# KNX-MCU-CONTROL_V0_2.net
KiCad netlist of a schematic drawn in Altium Designer
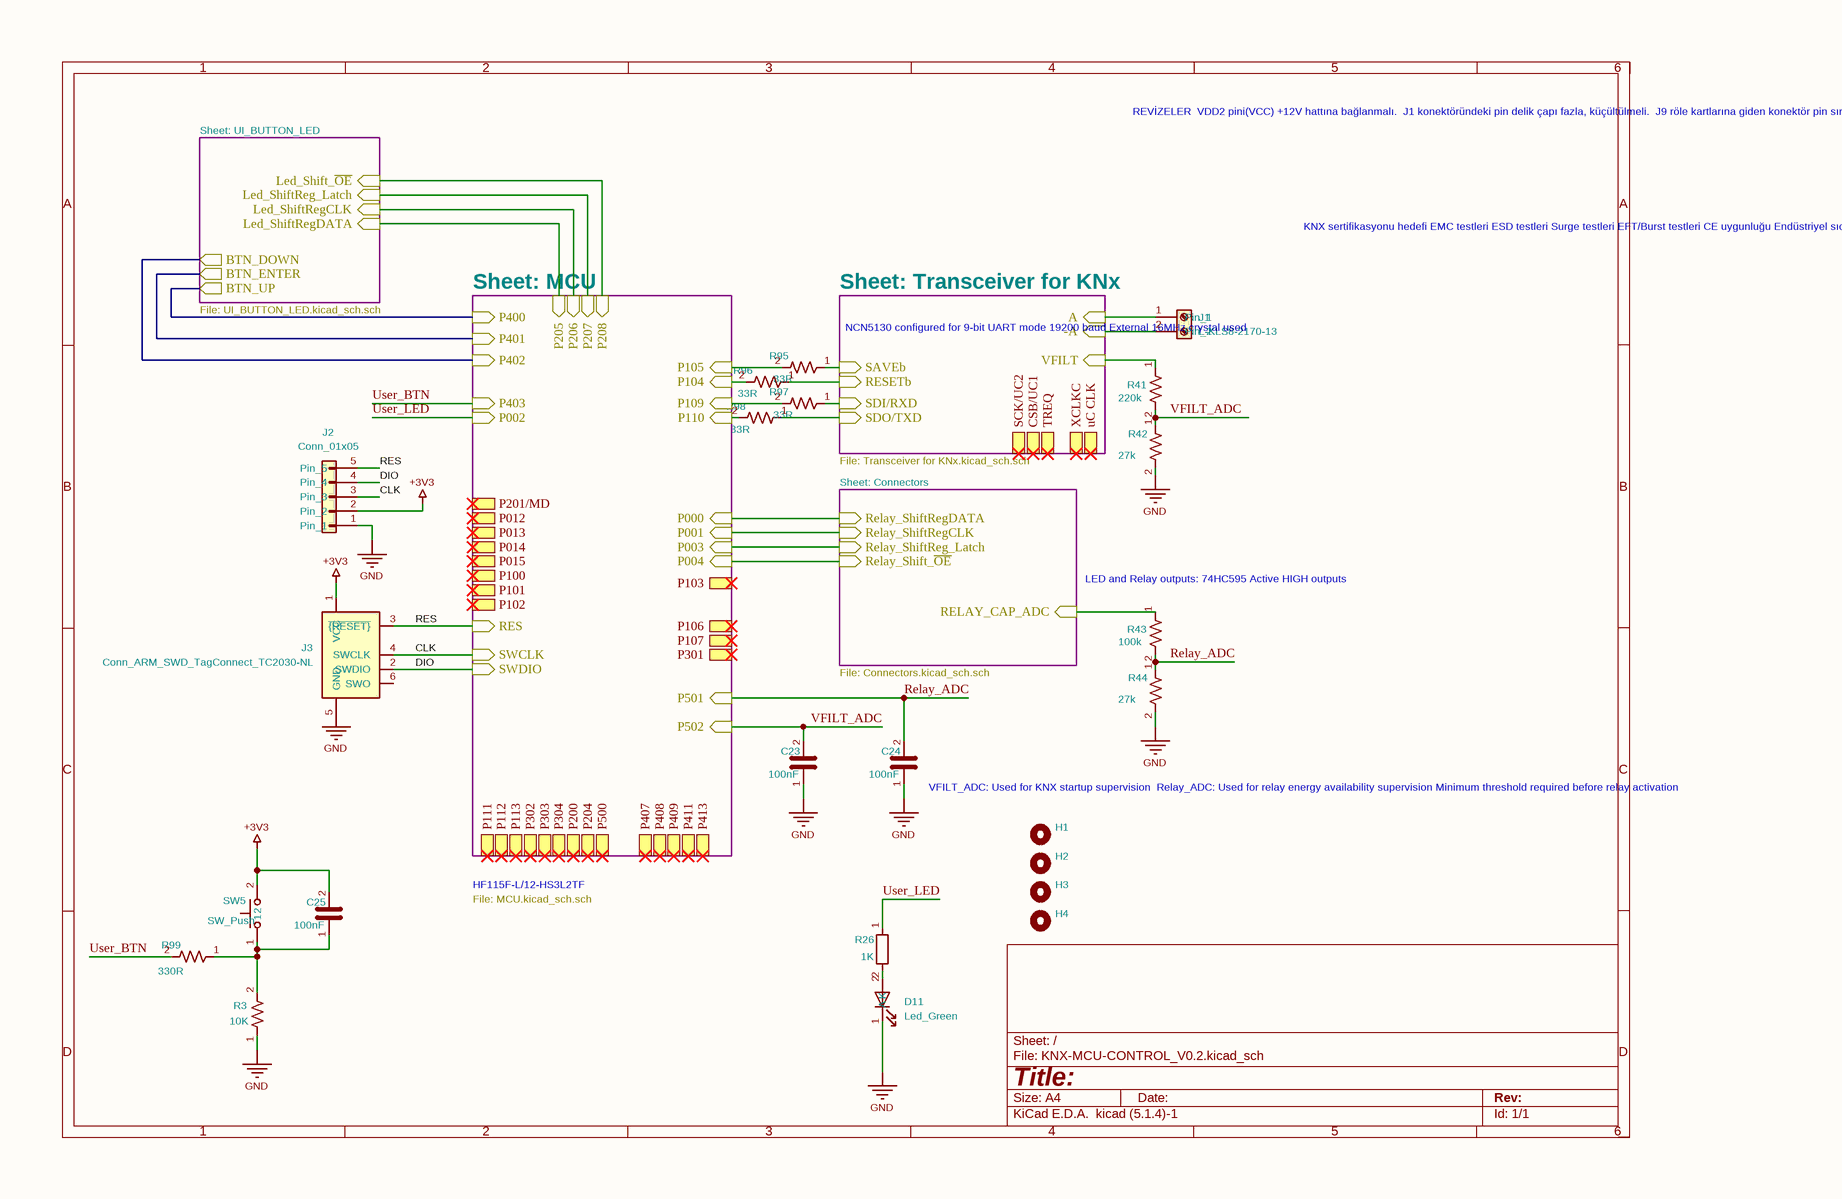
[diagram p0: KNX-MCU-CONTROL_V0.2.SchDoc]

(export (version "E")
  (design (tool "Eeschema 10.0.6"))
  (components
    (comp (ref "C23")
      (value "100nF")
      (footprint "C_0603_1608Metric")
      (fields
        (field (name "MANUFACTURER PART NUMBER") "CL10B104KB8NNNC")
        (field (name "MANUFACTURER") "Samsung Electro-Mechanics")
      )
      (libsource (lib "*") (part "C_1"))
    )
    (comp (ref "C24")
      (value "100nF")
      (footprint "C_0603_1608Metric")
      (fields
        (field (name "MANUFACTURER PART NUMBER") "CL10B104KB8NNNC")
        (field (name "MANUFACTURER") "Samsung Electro-Mechanics")
      )
      (libsource (lib "*") (part "C_1"))
    )
    (comp (ref "C25")
      (value "100nF")
      (footprint "C_0603_1608Metric")
      (fields
        (field (name "MANUFACTURER PART NUMBER") "CC0603KRX7R9BB104")
        (field (name "MANUFACTURER") "YAGEO")
      )
      (libsource (lib "*") (part "C_3"))
    )
    (comp (ref "D11")
      (value "Led_Green")
      (footprint "LED_D3.0mm")
      (fields
        (field (name "MANUFACTURER PART NUMBER") "TZ-L2-03YYBYG1GDJ30-001")
        (field (name "MANUFACTURER") "TUOZHAN")
      )
      (libsource (lib "Device") (part "LED"))
    )
    (comp (ref "H1")
      (value "YP-1132-20-0-N-0")
      (footprint "MountingHole_3mm")
      (description "YP-1132 Geçmeli Yükseltme Parçası (3.2mm delik için) İki Tarafı Kilitli")
      (fields (field (name "MANUFACTURER") "Altınkaya"))
      (libsource (lib "Mechanical") (part "MountingHole"))
    )
    (comp (ref "H2")
      (value "YP-1132-20-0-N-0")
      (footprint "MountingHole_3mm")
      (description "YP-1132 Geçmeli Yükseltme Parçası (3.2mm delik için) İki Tarafı Kilitli")
      (fields (field (name "MANUFACTURER") "Altınkaya"))
      (libsource (lib "Mechanical") (part "MountingHole"))
    )
    (comp (ref "H3")
      (value "YP-1132-20-0-N-0")
      (footprint "MountingHole_3mm")
      (description "YP-1132 Geçmeli Yükseltme Parçası (3.2mm delik için) İki Tarafı Kilitli")
      (fields (field (name "MANUFACTURER") "Altınkaya"))
      (libsource (lib "Mechanical") (part "MountingHole"))
    )
    (comp (ref "H4")
      (value "YP-1132-20-0-N-0")
      (footprint "MountingHole_3mm")
      (description "YP-1132 Geçmeli Yükseltme Parçası (3.2mm delik için) İki Tarafı Kilitli")
      (fields (field (name "MANUFACTURER") "Altınkaya"))
      (libsource (lib "Mechanical") (part "MountingHole"))
    )
    (comp (ref "J1")
      (value "L-KLS8-2170-13")
      (footprint "Samtec_HPM-02-01-x-S_Straight_1x02_Pitch5.08mm")
      (fields (field (name "MANUFACTURER") "KLS ELECTRONIC"))
      (libsource (lib "Connector") (part "Screw_Terminal_01x02"))
    )
    (comp (ref "J2")
      (value "Conn_01x05")
      (footprint "PinHeader_1x05_P2.54mm_Vertical")
      (libsource (lib "Connector_Generic") (part "Conn_01x05"))
    )
    (comp (ref "J3")
      (value "Conn_ARM_SWD_TagConnect_TC2030-NL")
      (footprint "Tag-Connect_TC2030-IDC-NL_2x03_P1.27mm_Vertical")
      (libsource (lib "Connector") (part "Conn_ARM_SWD_TagConnect_TC2030-NL"))
    )
    (comp (ref "R3")
      (value "10K")
      (footprint "R_0603_1608Metric")
      (fields (field (name "MANUFACTURER PART NUMBER") "FRC0603J103TS") (field (name "MANUFACTURER") "FOJAN"))
      (libsource (lib "Device") (part "R_US"))
    )
    (comp (ref "R26")
      (value "1K")
      (footprint "R_0603_1608Metric")
      (fields (field (name "MANUFACTURER PART NUMBER") "SCR0603J1K") (field (name "MANUFACTURER") "VO"))
      (libsource (lib "*") (part "R_7"))
    )
    (comp (ref "R41")
      (value "220k")
      (footprint "R_0603_1608Metric")
      (fields
        (field (name "MANUFACTURER PART NUMBER") "ERJ3EKF2203V")
        (field (name "MANUFACTURER") "PANASONIC")
      )
      (libsource (lib "Device") (part "R_US"))
    )
    (comp (ref "R42")
      (value "27k")
      (footprint "R_0603_1608Metric")
      (fields
        (field (name "MANUFACTURER PART NUMBER") "ERJ3EKF2702V")
        (field (name "MANUFACTURER") "PANASONIC")
      )
      (libsource (lib "Device") (part "R_US"))
    )
    (comp (ref "R43")
      (value "100k")
      (footprint "R_0603_1608Metric")
      (fields
        (field (name "MANUFACTURER PART NUMBER") "RC0603FR-07100KL")
        (field (name "MANUFACTURER") "YAGEO")
      )
      (libsource (lib "Device") (part "R_US"))
    )
    (comp (ref "R44")
      (value "27k")
      (footprint "R_0603_1608Metric")
      (fields
        (field (name "MANUFACTURER PART NUMBER") "ERJ3EKF2702V")
        (field (name "MANUFACTURER") "PANASONIC")
      )
      (libsource (lib "Device") (part "R_US"))
    )
    (comp (ref "R95")
      (value "33R")
      (footprint "R_0603_1608Metric")
      (fields
        (field (name "MANUFACTURER PART NUMBER") "0603SAF330JT5E")
        (field (name "MANUFACTURER") "ROYALOHM")
      )
      (libsource (lib "Device") (part "R_US"))
    )
    (comp (ref "R96")
      (value "33R")
      (footprint "R_0603_1608Metric")
      (fields
        (field (name "MANUFACTURER PART NUMBER") "0603SAF330JT5E")
        (field (name "MANUFACTURER") "ROYALOHM")
      )
      (libsource (lib "Device") (part "R_US"))
    )
    (comp (ref "R97")
      (value "33R")
      (footprint "R_0603_1608Metric")
      (fields
        (field (name "MANUFACTURER PART NUMBER") "0603SAF330JT5E")
        (field (name "MANUFACTURER") "ROYALOHM")
      )
      (libsource (lib "Device") (part "R_US"))
    )
    (comp (ref "R98")
      (value "33R")
      (footprint "R_0603_1608Metric")
      (fields
        (field (name "MANUFACTURER PART NUMBER") "0603SAF330JT5E")
        (field (name "MANUFACTURER") "ROYALOHM")
      )
      (libsource (lib "Device") (part "R_US"))
    )
    (comp (ref "R99")
      (value "330R")
      (footprint "R_0603_1608Metric")
      (fields
        (field (name "MANUFACTURER PART NUMBER") "FRC0603J331 TS")
        (field (name "MANUFACTURER") "FOJAN")
      )
      (libsource (lib "Device") (part "R_US"))
    )
    (comp (ref "SW5")
      (value "SW_Push")
      (footprint "SW_SPST_Omron_B3FS-100xP")
      (fields
        (field (name "MANUFACTURER PART NUMBER") "KH-12X12X8H-SMT")
        (field (name "MANUFACTURER") "kinghelm")
      )
      (libsource (lib "Switch") (part "SW_Push"))
    )
  )
  (nets
    (net (code "1") (name "+3V3") (class "Default")
      (node (ref "C25") (pin "2") (pinfunction "2_2") (pintype "passive"))
      (node (ref "J2") (pin "2") (pinfunction "Pin_2_2") (pintype "passive"))
      (node (ref "J3") (pin "1") (pinfunction "VCC_1") (pintype "passive"))
      (node (ref "SW5") (pin "2") (pinfunction "2_2") (pintype "passive"))
    )
    (net (code "2") (name "/-A") (class "Default")
      (node (ref "J1") (pin "2") (pinfunction "Pin_2_2") (pintype "passive"))
    )
    (net (code "3") (name "/A") (class "Default")
      (node (ref "J1") (pin "1") (pinfunction "Pin_1_1") (pintype "passive"))
    )
    (net (code "7") (name "/CLK") (class "Default")
      (node (ref "J2") (pin "3") (pinfunction "Pin_3_3") (pintype "passive"))
      (node (ref "J3") (pin "4") (pinfunction "SWCLK_4") (pintype "passive"))
    )
    (net (code "9") (name "/DIO") (class "Default")
      (node (ref "J2") (pin "4") (pinfunction "Pin_4_4") (pintype "passive"))
      (node (ref "J3") (pin "2") (pinfunction "SWDIO_2") (pintype "passive"))
    )
    (net (code "26") (name "/P104") (class "Default")
      (node (ref "R96") (pin "2") (pinfunction "2_2") (pintype "passive"))
    )
    (net (code "27") (name "/P105") (class "Default")
      (node (ref "R95") (pin "2") (pinfunction "2_2") (pintype "passive"))
    )
    (net (code "30") (name "/P109") (class "Default")
      (node (ref "R97") (pin "2") (pinfunction "2_2") (pintype "passive"))
    )
    (net (code "31") (name "/P110") (class "Default")
      (node (ref "R98") (pin "2") (pinfunction "2_2") (pintype "passive"))
    )
    (net (code "48") (name "/RELAY_CAP_ADC") (class "Default")
      (node (ref "R43") (pin "1") (pinfunction "1_1") (pintype "passive"))
    )
    (net (code "49") (name "/RES") (class "Default")
      (node (ref "J2") (pin "5") (pinfunction "Pin_5_5") (pintype "passive"))
      (node (ref "J3") (pin "3") (pinfunction "~{{RESET}}_3") (pintype "passive"))
    )
    (net (code "50") (name "/RESETb") (class "Default")
      (node (ref "R96") (pin "1") (pinfunction "1_1") (pintype "passive"))
    )
    (net (code "51") (name "/Relay_ADC") (class "Default")
      (node (ref "C24") (pin "2") (pinfunction "2_2") (pintype "passive"))
      (node (ref "R43") (pin "2") (pinfunction "2_2") (pintype "passive"))
      (node (ref "R44") (pin "1") (pinfunction "1_1") (pintype "passive"))
    )
    (net (code "52") (name "/SAVEb") (class "Default")
      (node (ref "R95") (pin "1") (pinfunction "1_1") (pintype "passive"))
    )
    (net (code "54") (name "/SDI{slash}RXD") (class "Default")
      (node (ref "R97") (pin "1") (pinfunction "1_1") (pintype "passive"))
    )
    (net (code "55") (name "/SDO{slash}TXD") (class "Default")
      (node (ref "R98") (pin "1") (pinfunction "1_1") (pintype "passive"))
    )
    (net (code "57") (name "/User_BTN") (class "Default")
      (node (ref "R99") (pin "2") (pinfunction "2_2") (pintype "passive"))
    )
    (net (code "58") (name "/User_LED") (class "Default")
      (node (ref "R26") (pin "1") (pinfunction "1_1") (pintype "passive"))
    )
    (net (code "59") (name "/VFILT") (class "Default")
      (node (ref "R41") (pin "1") (pinfunction "1_1") (pintype "passive"))
    )
    (net (code "60") (name "/VFILT_ADC") (class "Default")
      (node (ref "C23") (pin "2") (pinfunction "2_2") (pintype "passive"))
      (node (ref "R41") (pin "2") (pinfunction "2_2") (pintype "passive"))
      (node (ref "R42") (pin "1") (pinfunction "1_1") (pintype "passive"))
    )
    (net (code "63") (name "GND") (class "Default")
      (node (ref "C23") (pin "1") (pinfunction "1_1") (pintype "passive"))
      (node (ref "C24") (pin "1") (pinfunction "1_1") (pintype "passive"))
      (node (ref "D11") (pin "1") (pinfunction "K_1") (pintype "passive"))
      (node (ref "J2") (pin "1") (pinfunction "Pin_1_1") (pintype "passive"))
      (node (ref "J3") (pin "5") (pinfunction "GND_5") (pintype "passive"))
      (node (ref "R3") (pin "1") (pinfunction "1_1") (pintype "passive"))
      (node (ref "R42") (pin "2") (pinfunction "2_2") (pintype "passive"))
      (node (ref "R44") (pin "2") (pinfunction "2_2") (pintype "passive"))
    )
    (net (code "64") (name "Net-(C25-Pad1)") (class "Default")
      (node (ref "C25") (pin "1") (pinfunction "1_1") (pintype "passive"))
      (node (ref "R3") (pin "2") (pinfunction "2_2") (pintype "passive"))
      (node (ref "R99") (pin "1") (pinfunction "1_1") (pintype "passive"))
      (node (ref "SW5") (pin "1") (pinfunction "1_1") (pintype "passive"))
    )
    (net (code "65") (name "Net-(D11-A)") (class "Default")
      (node (ref "D11") (pin "2") (pinfunction "A_2") (pintype "passive"))
      (node (ref "R26") (pin "2") (pinfunction "2_2") (pintype "passive"))
    )
    (net (code "66") (name "unconnected-(J3-SWO-Pad6)") (class "Default")
      (node (ref "J3") (pin "6") (pinfunction "SWO_6") (pintype "passive"))
    )
  )
)
